# Ethernet.net
KiCad netlist of a schematic drawn in Altium Designer
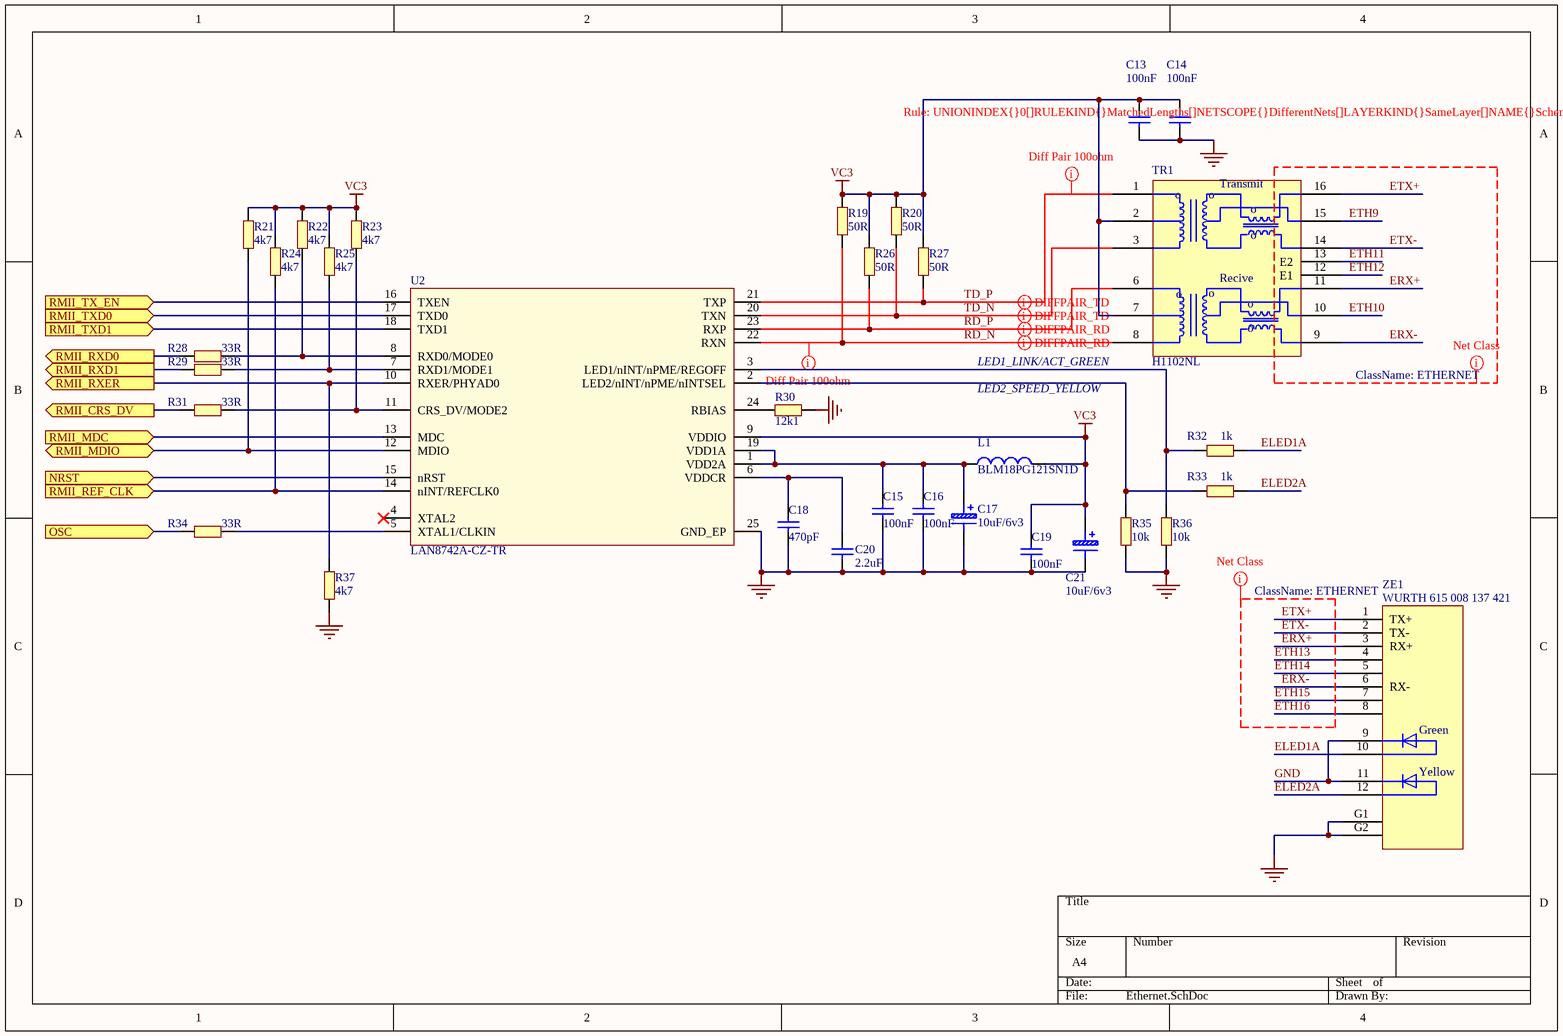
[diagram p0: Ethernet.SchDoc]

(export (version "E")
  (design (tool "Eeschema 10.0.6"))
  (components
    (comp (ref "C13")
      (value "100nF")
      (footprint "0603C")
      (description "Capacitor,100nF,16V,X7R,10%,0402,YAGEO")
      (libsource (lib "MCD_TOOLS") (part "Cap_100nF_X7R_10%_0402"))
    )
    (comp (ref "C14")
      (value "100nF")
      (footprint "0603C")
      (description "Capacitor,100nF,16V,X7R,10%,0402,YAGEO")
      (libsource (lib "MCD_TOOLS") (part "Cap_100nF_X7R_10%_0402"))
    )
    (comp (ref "C15")
      (value "100nF")
      (footprint "0603C")
      (description "Capacitor,100nF,16V,X7R,10%,0402,YAGEO")
      (libsource (lib "MCD_TOOLS") (part "Cap_100nF_X7R_10%_0402"))
    )
    (comp (ref "C16")
      (value "100nF")
      (footprint "0603C")
      (description "Capacitor,100nF,16V,X7R,10%,0402,YAGEO")
      (libsource (lib "MCD_TOOLS") (part "Cap_100nF_X7R_10%_0402"))
    )
    (comp (ref "C17") (value "10uF/6v3") (footprint "CAP_A") (libsource (lib "GkSchlib") (part "CapTantal")))
    (comp (ref "C18")
      (value "470pF")
      (footprint "0603C")
      (description "Capacitor,470pF,16V,X7R,10%,0402,YAGEO")
      (libsource (lib "MCD_TOOLS") (part "Cap_470pF_X7R_10%_0402"))
    )
    (comp (ref "C19")
      (value "100nF")
      (footprint "0603C")
      (description "Capacitor,100nF,16V,X7R,10%,0402,YAGEO")
      (libsource (lib "MCD_TOOLS") (part "Cap_100nF_X7R_10%_0402"))
    )
    (comp (ref "C20")
      (value "2.2uF")
      (footprint "0603C")
      (description "Capacitor,1uF,16V,X5R,10%,0603,YAGEO")
      (libsource (lib "MCD_TOOLS") (part "Cap_1uF_X5R_10%_0603"))
    )
    (comp (ref "C21") (value "10uF/6v3") (footprint "CAP_A") (libsource (lib "GkSchlib") (part "CapTantal")))
    (comp (ref "L1")
      (value "BLM18PG121SN1D")
      (footprint "0603L")
      (description "Bead,120R,2A,0603,BLM18PG121SN1D,MURATA")
      (libsource (lib "MCD_TOOLS") (part "BEAD_120R_2A_0603"))
    )
    (comp (ref "R19") (value "50R") (footprint "0603R") (libsource (lib "*") (part "RES3")))
    (comp (ref "R20") (value "50R") (footprint "0603R") (libsource (lib "*") (part "RES3")))
    (comp (ref "R21") (value "4k7") (footprint "0603R") (libsource (lib "*") (part "RES3")))
    (comp (ref "R22") (value "4k7") (footprint "0603R") (libsource (lib "") (part "RES3_1")))
    (comp (ref "R23") (value "4k7") (footprint "0603R") (libsource (lib "") (part "RES3_1")))
    (comp (ref "R24") (value "4k7") (footprint "0603R") (libsource (lib "*") (part "RES3")))
    (comp (ref "R25") (value "4k7") (footprint "0603R") (libsource (lib "") (part "RES3_1")))
    (comp (ref "R26") (value "50R") (footprint "0603R") (libsource (lib "*") (part "RES3")))
    (comp (ref "R27") (value "50R") (footprint "0603R") (libsource (lib "*") (part "RES3")))
    (comp (ref "R28") (value "33R") (footprint "0603R") (libsource (lib "") (part "RES3_3")))
    (comp (ref "R29") (value "33R") (footprint "0603R") (libsource (lib "") (part "RES3_3")))
    (comp (ref "R30") (value "12k1") (footprint "0603R") (libsource (lib "") (part "RES3_2")))
    (comp (ref "R31") (value "33R") (footprint "0603R") (libsource (lib "") (part "RES3_3")))
    (comp (ref "R32") (value "1k") (footprint "0603R") (libsource (lib "") (part "RES3_2")))
    (comp (ref "R33") (value "1k") (footprint "0603R") (libsource (lib "") (part "RES3_2")))
    (comp (ref "R34") (value "33R") (footprint "0603R") (libsource (lib "") (part "RES3_3")))
    (comp (ref "R35") (value "10k") (footprint "0603R") (libsource (lib "*") (part "RES3")))
    (comp (ref "R36") (value "10k") (footprint "0603R") (libsource (lib "*") (part "RES3")))
    (comp (ref "R37") (value "4k7") (footprint "0603R") (libsource (lib "*") (part "RES3")))
    (comp (ref "TR1") (value "H1102NL") (footprint "H1102") (libsource (lib "GkSchlib") (part "H1102NL")))
    (comp (ref "U2")
      (value "LAN8742A-CZ-TR")
      (footprint "QFN24_LAN")
      (libsource (lib "MCD_TOOLS") (part "LAN8742A-CZ-TR"))
    )
    (comp (ref "ZE1")
      (value "WURTH 615 008 137 421")
      (footprint "RJ45GELED")
      (libsource (lib "*") (part "RJ45GELED"))
    )
  )
  (nets
    (net (code "1") (name "/ELED1A") (class "Default")
      (node (ref "R32") (pin "1") (pintype "passive"))
      (node (ref "ZE1") (pin "10") (pintype "passive"))
    )
    (net (code "2") (name "/ELED2A") (class "Default")
      (node (ref "R33") (pin "1") (pintype "passive"))
      (node (ref "ZE1") (pin "12") (pintype "passive"))
    )
    (net (code "3") (name "/ERX+") (class "Default")
      (node (ref "TR1") (pin "11") (pinfunction "RO1_11") (pintype "passive"))
      (node (ref "ZE1") (pin "3") (pinfunction "RX+_3") (pintype "passive"))
    )
    (net (code "4") (name "/ERX-") (class "Default")
      (node (ref "TR1") (pin "9") (pinfunction "RO2_9") (pintype "passive"))
      (node (ref "ZE1") (pin "6") (pinfunction "RX-_6") (pintype "passive"))
    )
    (net (code "5") (name "/ETH9") (class "Default") (node (ref "TR1") (pin "15") (pintype "passive")))
    (net (code "6") (name "/ETH10") (class "Default") (node (ref "TR1") (pin "10") (pintype "passive")))
    (net (code "7") (name "/ETH11") (class "Default")
      (node (ref "TR1") (pin "13") (pinfunction "E2_13") (pintype "passive"))
    )
    (net (code "8") (name "/ETH12") (class "Default")
      (node (ref "TR1") (pin "12") (pinfunction "E1_12") (pintype "passive"))
    )
    (net (code "9") (name "/ETH13") (class "Default") (node (ref "ZE1") (pin "4") (pintype "passive")))
    (net (code "10") (name "/ETH14") (class "Default") (node (ref "ZE1") (pin "5") (pintype "passive")))
    (net (code "11") (name "/ETH15") (class "Default") (node (ref "ZE1") (pin "7") (pintype "passive")))
    (net (code "12") (name "/ETH16") (class "Default") (node (ref "ZE1") (pin "8") (pintype "passive")))
    (net (code "13") (name "/ETX+") (class "Default")
      (node (ref "TR1") (pin "16") (pinfunction "TO1_16") (pintype "passive"))
      (node (ref "ZE1") (pin "1") (pinfunction "TX+_1") (pintype "passive"))
    )
    (net (code "14") (name "/ETX-") (class "Default")
      (node (ref "TR1") (pin "14") (pinfunction "TO2_14") (pintype "passive"))
      (node (ref "ZE1") (pin "2") (pinfunction "TX-_2") (pintype "passive"))
    )
    (net (code "15") (name "/NRST") (class "Default")
      (node (ref "U2") (pin "15") (pinfunction "nRST_15") (pintype "passive"))
    )
    (net (code "16") (name "/OSC") (class "Default") (node (ref "R34") (pin "1") (pintype "passive")))
    (net (code "17") (name "/RD_N") (class "Default")
      (node (ref "R19") (pin "1") (pintype "passive"))
      (node (ref "TR1") (pin "8") (pinfunction "RI3_8") (pintype "passive"))
      (node (ref "U2") (pin "22") (pinfunction "RXN_22") (pintype "passive"))
    )
    (net (code "18") (name "/RD_P") (class "Default")
      (node (ref "R26") (pin "1") (pintype "passive"))
      (node (ref "TR1") (pin "6") (pinfunction "RI1_6") (pintype "passive"))
      (node (ref "U2") (pin "23") (pinfunction "RXP_23") (pintype "passive"))
    )
    (net (code "19") (name "/RMII_CRS_DV") (class "Default") (node (ref "R31") (pin "1") (pintype "passive")))
    (net (code "20") (name "/RMII_MDC") (class "Default")
      (node (ref "U2") (pin "13") (pinfunction "MDC_13") (pintype "passive"))
    )
    (net (code "21") (name "/RMII_MDIO") (class "Default")
      (node (ref "R21") (pin "1") (pintype "passive"))
      (node (ref "U2") (pin "12") (pinfunction "MDIO_12") (pintype "passive"))
    )
    (net (code "22") (name "/RMII_REF_CLK") (class "Default")
      (node (ref "R24") (pin "1") (pintype "passive"))
      (node (ref "U2") (pin "14") (pinfunction "nINT/REFCLK0_14") (pintype "passive"))
    )
    (net (code "23") (name "/RMII_RXD0") (class "Default") (node (ref "R28") (pin "1") (pintype "passive")))
    (net (code "24") (name "/RMII_RXD1") (class "Default") (node (ref "R29") (pin "1") (pintype "passive")))
    (net (code "25") (name "/RMII_RXER") (class "Default")
      (node (ref "R37") (pin "2") (pintype "passive"))
      (node (ref "U2") (pin "10") (pinfunction "RXER/PHYAD0_10") (pintype "passive"))
    )
    (net (code "26") (name "/RMII_TXD0") (class "Default")
      (node (ref "U2") (pin "17") (pinfunction "TXD0_17") (pintype "passive"))
    )
    (net (code "27") (name "/RMII_TXD1") (class "Default")
      (node (ref "U2") (pin "18") (pinfunction "TXD1_18") (pintype "passive"))
    )
    (net (code "28") (name "/RMII_TX_EN") (class "Default")
      (node (ref "U2") (pin "16") (pinfunction "TXEN_16") (pintype "passive"))
    )
    (net (code "29") (name "/TD_N") (class "Default")
      (node (ref "R20") (pin "1") (pintype "passive"))
      (node (ref "TR1") (pin "3") (pinfunction "TI3_3") (pintype "passive"))
      (node (ref "U2") (pin "20") (pinfunction "TXN_20") (pintype "passive"))
    )
    (net (code "30") (name "/TD_P") (class "Default")
      (node (ref "R27") (pin "1") (pintype "passive"))
      (node (ref "TR1") (pin "1") (pinfunction "TI1_1") (pintype "passive"))
      (node (ref "U2") (pin "21") (pinfunction "TXP_21") (pintype "passive"))
    )
    (net (code "31") (name "GND") (class "Default")
      (node (ref "C13") (pin "1") (pinfunction "1_1") (pintype "passive"))
      (node (ref "C14") (pin "1") (pinfunction "1_1") (pintype "passive"))
      (node (ref "C15") (pin "1") (pinfunction "1_1") (pintype "passive"))
      (node (ref "C16") (pin "1") (pinfunction "1_1") (pintype "passive"))
      (node (ref "C17") (pin "1") (pintype "passive"))
      (node (ref "C18") (pin "1") (pinfunction "1_1") (pintype "passive"))
      (node (ref "C19") (pin "1") (pinfunction "1_1") (pintype "passive"))
      (node (ref "C20") (pin "1") (pinfunction "1_1") (pintype "passive"))
      (node (ref "C21") (pin "1") (pintype "passive"))
      (node (ref "R30") (pin "1") (pintype "passive"))
      (node (ref "R35") (pin "1") (pintype "passive"))
      (node (ref "R36") (pin "1") (pintype "passive"))
      (node (ref "R37") (pin "1") (pintype "passive"))
      (node (ref "U2") (pin "25") (pinfunction "GND_EP_25") (pintype "passive"))
      (node (ref "ZE1") (pin "11") (pintype "passive"))
      (node (ref "ZE1") (pin "9") (pintype "passive"))
      (node (ref "ZE1") (pin "G1") (pintype "passive"))
      (node (ref "ZE1") (pin "G2") (pintype "passive"))
    )
    (net (code "32") (name "Net-(U2-CRS_DV{slash}MODE2)") (class "Default")
      (node (ref "R23") (pin "2") (pintype "passive"))
      (node (ref "R31") (pin "2") (pintype "passive"))
      (node (ref "U2") (pin "11") (pinfunction "CRS_DV/MODE2_11") (pintype "passive"))
    )
    (net (code "33") (name "Net-(U2-LED1{slash}nINT{slash}nPME{slash}REGOFF)") (class "Default")
      (node (ref "R32") (pin "2") (pintype "passive"))
      (node (ref "R36") (pin "2") (pintype "passive"))
      (node (ref "U2") (pin "3") (pinfunction "LED1/nINT/nPME/REGOFF_3") (pintype "passive"))
    )
    (net (code "34") (name "Net-(U2-LED2{slash}nINT{slash}nPME{slash}nINTSEL)") (class "Default")
      (node (ref "R33") (pin "2") (pintype "passive"))
      (node (ref "R35") (pin "2") (pintype "passive"))
      (node (ref "U2") (pin "2") (pinfunction "LED2/nINT/nPME/nINTSEL_2") (pintype "passive"))
    )
    (net (code "35") (name "Net-(U2-RBIAS)") (class "Default")
      (node (ref "R30") (pin "2") (pintype "passive"))
      (node (ref "U2") (pin "24") (pinfunction "RBIAS_24") (pintype "passive"))
    )
    (net (code "36") (name "Net-(U2-RXD0{slash}MODE0)") (class "Default")
      (node (ref "R22") (pin "2") (pintype "passive"))
      (node (ref "R28") (pin "2") (pintype "passive"))
      (node (ref "U2") (pin "8") (pinfunction "RXD0/MODE0_8") (pintype "passive"))
    )
    (net (code "37") (name "Net-(U2-RXD1{slash}MODE1)") (class "Default")
      (node (ref "R25") (pin "2") (pintype "passive"))
      (node (ref "R29") (pin "2") (pintype "passive"))
      (node (ref "U2") (pin "7") (pinfunction "RXD1/MODE1_7") (pintype "passive"))
    )
    (net (code "38") (name "Net-(U2-VDD1A)") (class "Default")
      (node (ref "C15") (pin "2") (pinfunction "2_2") (pintype "passive"))
      (node (ref "C16") (pin "2") (pinfunction "2_2") (pintype "passive"))
      (node (ref "C17") (pin "2") (pintype "passive"))
      (node (ref "L1") (pin "1") (pinfunction "1_1") (pintype "passive"))
      (node (ref "U2") (pin "1") (pinfunction "VDD2A_1") (pintype "passive"))
      (node (ref "U2") (pin "19") (pinfunction "VDD1A_19") (pintype "passive"))
    )
    (net (code "39") (name "Net-(U2-VDDCR)") (class "Default")
      (node (ref "C18") (pin "2") (pinfunction "2_2") (pintype "passive"))
      (node (ref "C20") (pin "2") (pinfunction "2_2") (pintype "passive"))
      (node (ref "U2") (pin "6") (pinfunction "VDDCR_6") (pintype "passive"))
    )
    (net (code "40") (name "Net-(U2-XTAL1{slash}CLKIN)") (class "Default")
      (node (ref "R34") (pin "2") (pintype "passive"))
      (node (ref "U2") (pin "5") (pinfunction "XTAL1/CLKIN_5") (pintype "passive"))
    )
    (net (code "41") (name "VC3") (class "Default")
      (node (ref "C13") (pin "2") (pinfunction "2_2") (pintype "passive"))
      (node (ref "C14") (pin "2") (pinfunction "2_2") (pintype "passive"))
      (node (ref "C19") (pin "2") (pinfunction "2_2") (pintype "passive"))
      (node (ref "C21") (pin "2") (pintype "passive"))
      (node (ref "L1") (pin "2") (pinfunction "2_2") (pintype "passive"))
      (node (ref "R19") (pin "2") (pintype "passive"))
      (node (ref "R20") (pin "2") (pintype "passive"))
      (node (ref "R21") (pin "2") (pintype "passive"))
      (node (ref "R22") (pin "1") (pintype "passive"))
      (node (ref "R23") (pin "1") (pintype "passive"))
      (node (ref "R24") (pin "2") (pintype "passive"))
      (node (ref "R25") (pin "1") (pintype "passive"))
      (node (ref "R26") (pin "2") (pintype "passive"))
      (node (ref "R27") (pin "2") (pintype "passive"))
      (node (ref "TR1") (pin "2") (pinfunction "TI2_2") (pintype "passive"))
      (node (ref "TR1") (pin "7") (pinfunction "RI2_7") (pintype "passive"))
      (node (ref "U2") (pin "9") (pinfunction "VDDIO_9") (pintype "passive"))
    )
    (net (code "42") (name "unconnected-(U2-XTAL2-Pad4)") (class "Default")
      (node (ref "U2") (pin "4") (pinfunction "XTAL2_4") (pintype "passive+no_connect"))
    )
  )
)
